# power.net
KiCad netlist of a schematic drawn in Altium Designer
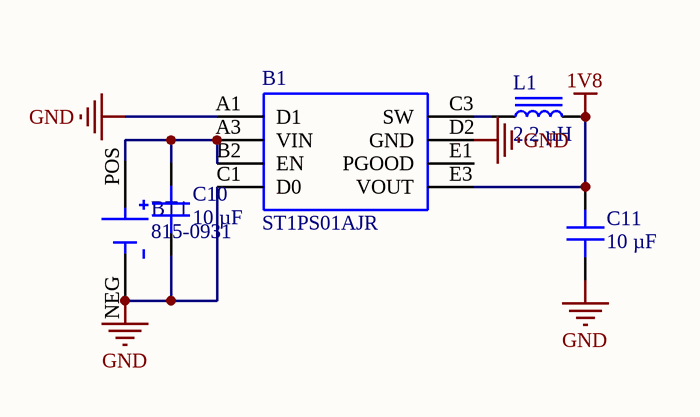
[diagram p0: power.SchDoc]

(export (version "E")
  (design (tool "Eeschema 10.0.6"))
  (components
    (comp (ref "B1")
      (value "ST1PS01AJR")
      (footprint "ST1PS01AJR")
      (fields (field (name "MOUSER PART NUMBER") "511-ST1PS01AJR"))
      (libsource (lib "ST1PS01AJR") (part "ST1PS01AJR"))
    )
    (comp (ref "BT1")
      (value "815-0931")
      (footprint "BAT_815-0931")
      (description "Holder 1/2aa Battery w/o Cover")
      (libsource (lib "815-0931") (part "815-0931"))
    )
    (comp (ref "C10")
      (value "10 µF")
      (footprint "CAP 0603_1608")
      (description "CAP CER 10UF 6.3V X5R 0603")
      (fields
        (field (name "PART NUMBER") "GRM188R60J106ME47D")
        (field (name "MANUFACTURER") "Murata Electronics")
      )
      (libsource (lib "Celestial Altium Library - altium_library") (part "Capacitor"))
    )
    (comp (ref "C11")
      (value "10 µF")
      (footprint "CAP 0603_1608")
      (description "CAP CER 10UF 6.3V X5R 0603")
      (fields
        (field (name "PART NUMBER") "GRM188R60J106ME47D")
        (field (name "MANUFACTURER") "Murata Electronics")
      )
      (libsource (lib "Celestial Altium Library - altium_library") (part "Capacitor"))
    )
    (comp (ref "L1")
      (value "2.2 µH")
      (footprint "TDK VLS201612CX")
      (description "FIXED IND 6.8UH 930MA 368MOHM SM")
      (fields
        (field (name "PART NUMBER") "VLS201612CX-6R8M-1")
        (field (name "MANUFACTURER") "TDK Corporation")
      )
      (libsource (lib "Celestial Altium Library - altium_library") (part "Inductor"))
    )
  )
  (nets
    (net (code "1") (name "1V8") (class "Default")
      (node (ref "B1") (pin "E3") (pinfunction "VOUT_E3") (pintype "passive"))
      (node (ref "C11") (pin "2") (pinfunction "2_2") (pintype "passive"))
      (node (ref "L1") (pin "2") (pinfunction "2_2") (pintype "passive"))
    )
    (net (code "2") (name "GND") (class "Default")
      (node (ref "B1") (pin "A1") (pinfunction "D1_A1") (pintype "passive"))
      (node (ref "B1") (pin "C1") (pinfunction "D0_C1") (pintype "passive"))
      (node (ref "B1") (pin "D2") (pinfunction "GND_D2") (pintype "passive"))
      (node (ref "BT1") (pin "NEG") (pinfunction "NEG_NEG") (pintype "passive"))
      (node (ref "C10") (pin "1") (pinfunction "1_1") (pintype "passive"))
      (node (ref "C11") (pin "1") (pinfunction "1_1") (pintype "passive"))
    )
    (net (code "3") (name "Net-(B1-EN)") (class "Default")
      (node (ref "B1") (pin "A3") (pinfunction "VIN_A3") (pintype "passive"))
      (node (ref "B1") (pin "B2") (pinfunction "EN_B2") (pintype "passive"))
      (node (ref "BT1") (pin "POS") (pinfunction "POS_POS") (pintype "passive"))
      (node (ref "C10") (pin "2") (pinfunction "2_2") (pintype "passive"))
    )
    (net (code "4") (name "Net-(B1-SW)") (class "Default")
      (node (ref "B1") (pin "C3") (pinfunction "SW_C3") (pintype "passive"))
      (node (ref "L1") (pin "1") (pinfunction "1_1") (pintype "passive"))
    )
    (net (code "5") (name "unconnected-(B1-PGOOD-PadE1)") (class "Default")
      (node (ref "B1") (pin "E1") (pinfunction "PGOOD_E1") (pintype "passive"))
    )
  )
)
